# TIVA_SHIELD_Ver_2_0.net
KiCad netlist of a schematic drawn in EAGLE
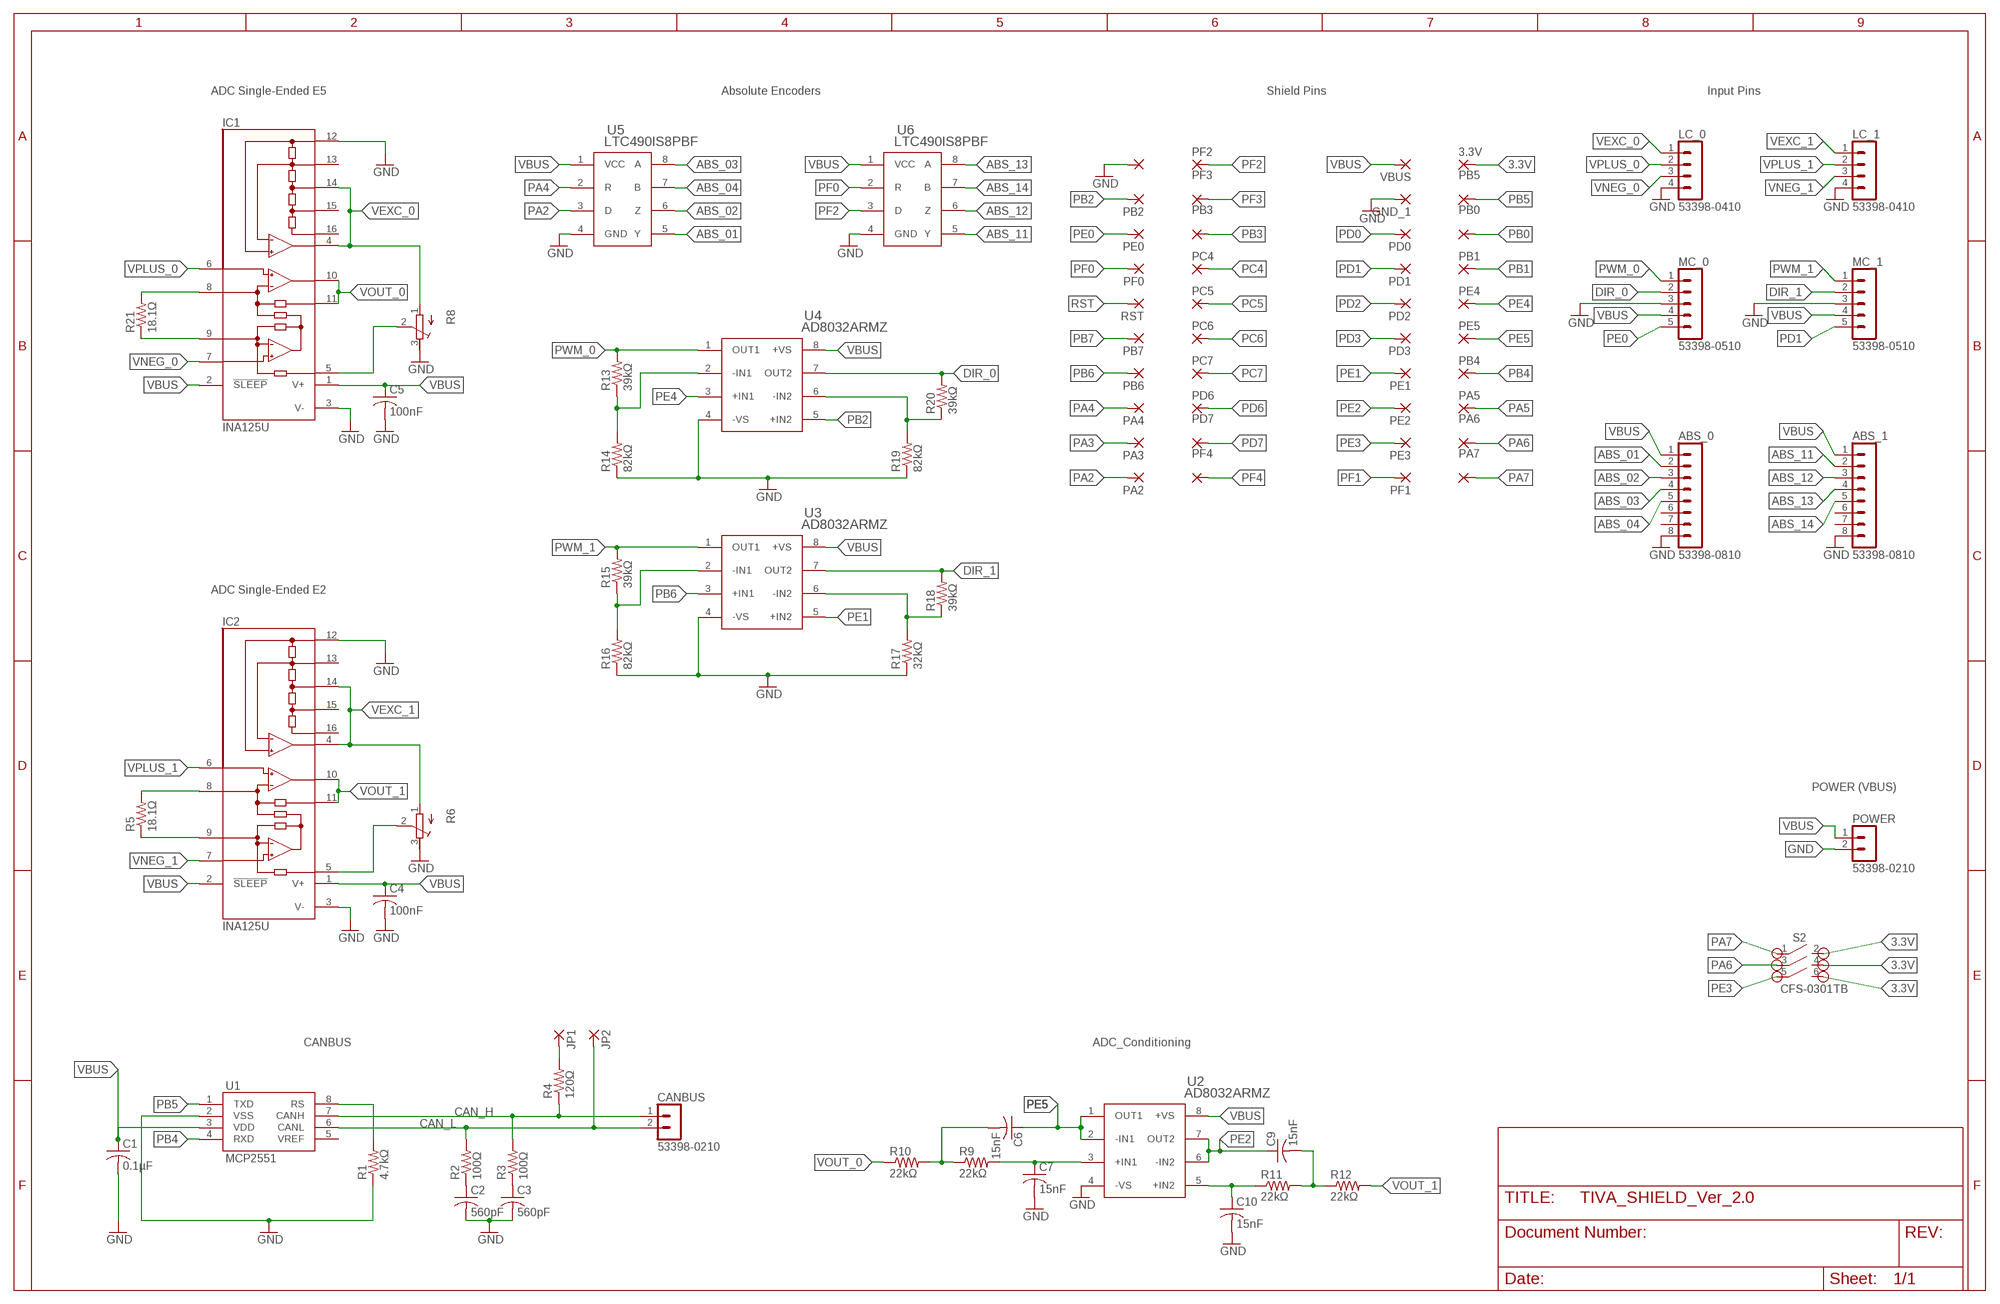
[diagram p0: schematic, sheet 1]

(export (version "E")
  (design (tool "Eeschema 10.0.6"))
  (components
    (comp (ref "3.3V")
      (value "1,6/0,9")
      (footprint "eagle-import:1,6_0,9")
      (libsource (lib "eagle-import") (part "1,6/0,9"))
    )
    (comp (ref "ABS_0")
      (value "53398-0810")
      (footprint "eagle-import:53398-0810")
      (libsource (lib "eagle-import") (part "53398-0810"))
    )
    (comp (ref "ABS_1")
      (value "53398-0810")
      (footprint "eagle-import:53398-0810")
      (libsource (lib "eagle-import") (part "53398-0810"))
    )
    (comp (ref "C1")
      (value "0.1µF")
      (footprint "eagle-import:C0805")
      (libsource (lib "eagle-import") (part "C-USC0805"))
    )
    (comp (ref "C2")
      (value "560pF")
      (footprint "eagle-import:C0805")
      (libsource (lib "eagle-import") (part "C-USC0805"))
    )
    (comp (ref "C3")
      (value "560pF")
      (footprint "eagle-import:C0805")
      (libsource (lib "eagle-import") (part "C-USC0805"))
    )
    (comp (ref "C4")
      (value "100nF")
      (footprint "eagle-import:C0805")
      (libsource (lib "eagle-import") (part "C-USC0805"))
    )
    (comp (ref "C5")
      (value "100nF")
      (footprint "eagle-import:C0805")
      (libsource (lib "eagle-import") (part "C-USC0805"))
    )
    (comp (ref "C6")
      (value "15nF")
      (footprint "eagle-import:C0805")
      (libsource (lib "eagle-import") (part "C-USC0805"))
    )
    (comp (ref "C7")
      (value "15nF")
      (footprint "eagle-import:C0805")
      (libsource (lib "eagle-import") (part "C-USC0805"))
    )
    (comp (ref "C9")
      (value "15nF")
      (footprint "eagle-import:C0805")
      (libsource (lib "eagle-import") (part "C-USC0805"))
    )
    (comp (ref "C10")
      (value "15nF")
      (footprint "eagle-import:C0805")
      (libsource (lib "eagle-import") (part "C-USC0805"))
    )
    (comp (ref "CANBUS")
      (value "53398-0210")
      (footprint "eagle-import:53398-0210")
      (libsource (lib "eagle-import") (part "53398-0210"))
    )
    (comp (ref "GND_0")
      (value "1,6/0,9")
      (footprint "eagle-import:1,6_0,9")
      (libsource (lib "eagle-import") (part "1,6/0,9"))
    )
    (comp (ref "GND_1")
      (value "1,6/0,9")
      (footprint "eagle-import:1,6_0,9")
      (libsource (lib "eagle-import") (part "1,6/0,9"))
    )
    (comp (ref "IC1")
      (value "INA125U")
      (footprint "eagle-import:SO16-1")
      (fields (field (name "MF") "TEXAS INSTRUMENT CONNECTORS"))
      (libsource (lib "eagle-import") (part "INA125U"))
    )
    (comp (ref "IC2")
      (value "INA125U")
      (footprint "eagle-import:SO16-1")
      (fields (field (name "MF") "TEXAS INSTRUMENT CONNECTORS"))
      (libsource (lib "eagle-import") (part "INA125U"))
    )
    (comp (ref "JP1")
      (value "1,6/0,9")
      (footprint "eagle-import:1,6_0,9")
      (libsource (lib "eagle-import") (part "1,6/0,9"))
    )
    (comp (ref "JP2")
      (value "1,6/0,9")
      (footprint "eagle-import:1,6_0,9")
      (libsource (lib "eagle-import") (part "1,6/0,9"))
    )
    (comp (ref "LC_0")
      (value "53398-0410")
      (footprint "eagle-import:53398-0410")
      (libsource (lib "eagle-import") (part "53398-0410"))
    )
    (comp (ref "LC_1")
      (value "53398-0410")
      (footprint "eagle-import:53398-0410")
      (libsource (lib "eagle-import") (part "53398-0410"))
    )
    (comp (ref "MC_0")
      (value "53398-0510")
      (footprint "eagle-import:53398-0510")
      (libsource (lib "eagle-import") (part "53398-0510"))
    )
    (comp (ref "MC_1")
      (value "53398-0510")
      (footprint "eagle-import:53398-0510")
      (libsource (lib "eagle-import") (part "53398-0510"))
    )
    (comp (ref "PA2")
      (value "1,6/0,9")
      (footprint "eagle-import:1,6_0,9")
      (libsource (lib "eagle-import") (part "1,6/0,9"))
    )
    (comp (ref "PA3")
      (value "1,6/0,9")
      (footprint "eagle-import:1,6_0,9")
      (libsource (lib "eagle-import") (part "1,6/0,9"))
    )
    (comp (ref "PA4")
      (value "1,6/0,9")
      (footprint "eagle-import:1,6_0,9")
      (libsource (lib "eagle-import") (part "1,6/0,9"))
    )
    (comp (ref "PA5")
      (value "1,6/0,9")
      (footprint "eagle-import:1,6_0,9")
      (libsource (lib "eagle-import") (part "1,6/0,9"))
    )
    (comp (ref "PA6")
      (value "1,6/0,9")
      (footprint "eagle-import:1,6_0,9")
      (libsource (lib "eagle-import") (part "1,6/0,9"))
    )
    (comp (ref "PA7")
      (value "1,6/0,9")
      (footprint "eagle-import:1,6_0,9")
      (libsource (lib "eagle-import") (part "1,6/0,9"))
    )
    (comp (ref "PB0")
      (value "1,6/0,9")
      (footprint "eagle-import:1,6_0,9")
      (libsource (lib "eagle-import") (part "1,6/0,9"))
    )
    (comp (ref "PB1")
      (value "1,6/0,9")
      (footprint "eagle-import:1,6_0,9")
      (libsource (lib "eagle-import") (part "1,6/0,9"))
    )
    (comp (ref "PB2")
      (value "1,6/0,9")
      (footprint "eagle-import:1,6_0,9")
      (libsource (lib "eagle-import") (part "1,6/0,9"))
    )
    (comp (ref "PB3")
      (value "1,6/0,9")
      (footprint "eagle-import:1,6_0,9")
      (libsource (lib "eagle-import") (part "1,6/0,9"))
    )
    (comp (ref "PB4")
      (value "1,6/0,9")
      (footprint "eagle-import:1,6_0,9")
      (libsource (lib "eagle-import") (part "1,6/0,9"))
    )
    (comp (ref "PB5")
      (value "1,6/0,9")
      (footprint "eagle-import:1,6_0,9")
      (libsource (lib "eagle-import") (part "1,6/0,9"))
    )
    (comp (ref "PB6")
      (value "1,6/0,9")
      (footprint "eagle-import:1,6_0,9")
      (libsource (lib "eagle-import") (part "1,6/0,9"))
    )
    (comp (ref "PB7")
      (value "1,6/0,9")
      (footprint "eagle-import:1,6_0,9")
      (libsource (lib "eagle-import") (part "1,6/0,9"))
    )
    (comp (ref "PC4")
      (value "1,6/0,9")
      (footprint "eagle-import:1,6_0,9")
      (libsource (lib "eagle-import") (part "1,6/0,9"))
    )
    (comp (ref "PC5")
      (value "1,6/0,9")
      (footprint "eagle-import:1,6_0,9")
      (libsource (lib "eagle-import") (part "1,6/0,9"))
    )
    (comp (ref "PC6")
      (value "1,6/0,9")
      (footprint "eagle-import:1,6_0,9")
      (libsource (lib "eagle-import") (part "1,6/0,9"))
    )
    (comp (ref "PC7")
      (value "1,6/0,9")
      (footprint "eagle-import:1,6_0,9")
      (libsource (lib "eagle-import") (part "1,6/0,9"))
    )
    (comp (ref "PD0")
      (value "1,6/0,9")
      (footprint "eagle-import:1,6_0,9")
      (libsource (lib "eagle-import") (part "1,6/0,9"))
    )
    (comp (ref "PD1")
      (value "1,6/0,9")
      (footprint "eagle-import:1,6_0,9")
      (libsource (lib "eagle-import") (part "1,6/0,9"))
    )
    (comp (ref "PD2")
      (value "1,6/0,9")
      (footprint "eagle-import:1,6_0,9")
      (libsource (lib "eagle-import") (part "1,6/0,9"))
    )
    (comp (ref "PD3")
      (value "1,6/0,9")
      (footprint "eagle-import:1,6_0,9")
      (libsource (lib "eagle-import") (part "1,6/0,9"))
    )
    (comp (ref "PD6")
      (value "1,6/0,9")
      (footprint "eagle-import:1,6_0,9")
      (libsource (lib "eagle-import") (part "1,6/0,9"))
    )
    (comp (ref "PD7")
      (value "1,6/0,9")
      (footprint "eagle-import:1,6_0,9")
      (libsource (lib "eagle-import") (part "1,6/0,9"))
    )
    (comp (ref "PE0")
      (value "1,6/0,9")
      (footprint "eagle-import:1,6_0,9")
      (libsource (lib "eagle-import") (part "1,6/0,9"))
    )
    (comp (ref "PE1")
      (value "1,6/0,9")
      (footprint "eagle-import:1,6_0,9")
      (libsource (lib "eagle-import") (part "1,6/0,9"))
    )
    (comp (ref "PE2")
      (value "1,6/0,9")
      (footprint "eagle-import:1,6_0,9")
      (libsource (lib "eagle-import") (part "1,6/0,9"))
    )
    (comp (ref "PE3")
      (value "1,6/0,9")
      (footprint "eagle-import:1,6_0,9")
      (libsource (lib "eagle-import") (part "1,6/0,9"))
    )
    (comp (ref "PE4")
      (value "1,6/0,9")
      (footprint "eagle-import:1,6_0,9")
      (libsource (lib "eagle-import") (part "1,6/0,9"))
    )
    (comp (ref "PE5")
      (value "1,6/0,9")
      (footprint "eagle-import:1,6_0,9")
      (libsource (lib "eagle-import") (part "1,6/0,9"))
    )
    (comp (ref "PF0")
      (value "1,6/0,9")
      (footprint "eagle-import:1,6_0,9")
      (libsource (lib "eagle-import") (part "1,6/0,9"))
    )
    (comp (ref "PF1")
      (value "1,6/0,9")
      (footprint "eagle-import:1,6_0,9")
      (libsource (lib "eagle-import") (part "1,6/0,9"))
    )
    (comp (ref "PF2")
      (value "1,6/0,9")
      (footprint "eagle-import:1,6_0,9")
      (libsource (lib "eagle-import") (part "1,6/0,9"))
    )
    (comp (ref "PF3")
      (value "1,6/0,9")
      (footprint "eagle-import:1,6_0,9")
      (libsource (lib "eagle-import") (part "1,6/0,9"))
    )
    (comp (ref "PF4")
      (value "1,6/0,9")
      (footprint "eagle-import:1,6_0,9")
      (libsource (lib "eagle-import") (part "1,6/0,9"))
    )
    (comp (ref "POWER")
      (value "53398-0210")
      (footprint "eagle-import:53398-0210")
      (libsource (lib "eagle-import") (part "53398-0210"))
    )
    (comp (ref "R1")
      (value "4.7kΩ")
      (footprint "eagle-import:R0805")
      (libsource (lib "eagle-import") (part "R-US_R0805"))
    )
    (comp (ref "R2")
      (value "100Ω")
      (footprint "eagle-import:R0805")
      (libsource (lib "eagle-import") (part "R-US_R0805"))
    )
    (comp (ref "R3")
      (value "100Ω")
      (footprint "eagle-import:R0805")
      (libsource (lib "eagle-import") (part "R-US_R0805"))
    )
    (comp (ref "R4")
      (value "120Ω")
      (footprint "eagle-import:R0805")
      (libsource (lib "eagle-import") (part "R-US_R0805"))
    )
    (comp (ref "R5")
      (value "18.1Ω")
      (footprint "eagle-import:R0805")
      (libsource (lib "eagle-import") (part "R-US_R0805"))
    )
    (comp (ref "R6")
      (value "R-TRIMM64W")
      (footprint "eagle-import:RTRIM64W")
      (libsource (lib "eagle-import") (part "R-TRIMM64W"))
    )
    (comp (ref "R8")
      (value "R-TRIMM64W")
      (footprint "eagle-import:RTRIM64W")
      (libsource (lib "eagle-import") (part "R-TRIMM64W"))
    )
    (comp (ref "R9")
      (value "22kΩ")
      (footprint "eagle-import:R0805")
      (libsource (lib "eagle-import") (part "R-US_R0805"))
    )
    (comp (ref "R10")
      (value "22kΩ")
      (footprint "eagle-import:R0805")
      (libsource (lib "eagle-import") (part "R-US_R0805"))
    )
    (comp (ref "R11")
      (value "22kΩ")
      (footprint "eagle-import:R0805")
      (libsource (lib "eagle-import") (part "R-US_R0805"))
    )
    (comp (ref "R12")
      (value "22kΩ")
      (footprint "eagle-import:R0805")
      (libsource (lib "eagle-import") (part "R-US_R0805"))
    )
    (comp (ref "R13")
      (value "39kΩ")
      (footprint "eagle-import:R0805")
      (libsource (lib "eagle-import") (part "R-US_R0805"))
    )
    (comp (ref "R14")
      (value "82kΩ")
      (footprint "eagle-import:R0805")
      (libsource (lib "eagle-import") (part "R-US_R0805"))
    )
    (comp (ref "R15")
      (value "39kΩ")
      (footprint "eagle-import:R0805")
      (libsource (lib "eagle-import") (part "R-US_R0805"))
    )
    (comp (ref "R16")
      (value "82kΩ")
      (footprint "eagle-import:R0805")
      (libsource (lib "eagle-import") (part "R-US_R0805"))
    )
    (comp (ref "R17")
      (value "32kΩ")
      (footprint "eagle-import:R0805")
      (libsource (lib "eagle-import") (part "R-US_R0805"))
    )
    (comp (ref "R18")
      (value "39kΩ")
      (footprint "eagle-import:R0805")
      (libsource (lib "eagle-import") (part "R-US_R0805"))
    )
    (comp (ref "R19")
      (value "82kΩ")
      (footprint "eagle-import:R0805")
      (libsource (lib "eagle-import") (part "R-US_R0805"))
    )
    (comp (ref "R20")
      (value "39kΩ")
      (footprint "eagle-import:R0805")
      (libsource (lib "eagle-import") (part "R-US_R0805"))
    )
    (comp (ref "R21")
      (value "18.1Ω")
      (footprint "eagle-import:R0805")
      (libsource (lib "eagle-import") (part "R-US_R0805"))
    )
    (comp (ref "RST")
      (value "1,6/0,9")
      (footprint "eagle-import:1,6_0,9")
      (libsource (lib "eagle-import") (part "1,6/0,9"))
    )
    (comp (ref "S2")
      (value "CFS-0301TB")
      (footprint "eagle-import:CFS-0301TB")
      (libsource (lib "eagle-import") (part "CFS-0301TBSMD"))
    )
    (comp (ref "U1")
      (value "MCP2551")
      (footprint "eagle-import:SO08")
      (libsource (lib "eagle-import") (part "MCP2551"))
    )
    (comp (ref "U2")
      (value "AD8032ARMZ")
      (footprint "eagle-import:RM_8")
      (libsource (lib "eagle-import") (part "AD8032ARMZ"))
    )
    (comp (ref "U3")
      (value "AD8032ARMZ")
      (footprint "eagle-import:RM_8")
      (libsource (lib "eagle-import") (part "AD8032ARMZ"))
    )
    (comp (ref "U4")
      (value "AD8032ARMZ")
      (footprint "eagle-import:RM_8")
      (libsource (lib "eagle-import") (part "AD8032ARMZ"))
    )
    (comp (ref "U5")
      (value "LTC490IS8PBF")
      (footprint "eagle-import:SO-8_S")
      (fields (field (name "MANUFACTURER_PART_NUMBER") "LTC490IS8#PBF"))
      (libsource (lib "eagle-import") (part "LTC490IS8PBF"))
    )
    (comp (ref "U6")
      (value "LTC490IS8PBF")
      (footprint "eagle-import:SO-8_S")
      (fields (field (name "MANUFACTURER_PART_NUMBER") "LTC490IS8#PBF"))
      (libsource (lib "eagle-import") (part "LTC490IS8PBF"))
    )
    (comp (ref "VBUS")
      (value "1,6/0,9")
      (footprint "eagle-import:1,6_0,9")
      (libsource (lib "eagle-import") (part "1,6/0,9"))
    )
  )
  (nets
    (net (code "1") (name "/CAN_H") (class "Default")
      (node (ref "CANBUS") (pin "1") (pinfunction "1_1") (pintype "passive"))
      (node (ref "R3") (pin "2") (pinfunction "2_2") (pintype "passive"))
      (node (ref "R4") (pin "1") (pinfunction "1_1") (pintype "passive"))
      (node (ref "U1") (pin "7") (pinfunction "CANH_7") (pintype "bidirectional"))
    )
    (net (code "2") (name "/CAN_L") (class "Default")
      (node (ref "CANBUS") (pin "2") (pinfunction "2_2") (pintype "passive"))
      (node (ref "JP2") (pin "1") (pinfunction "P_1") (pintype "passive"))
      (node (ref "R2") (pin "2") (pinfunction "2_2") (pintype "passive"))
      (node (ref "U1") (pin "6") (pinfunction "CANL_6") (pintype "bidirectional"))
    )
    (net (code "3") (name "3.3V") (class "Default")
      (node (ref "3.3V") (pin "1") (pinfunction "P_1") (pintype "passive"))
      (node (ref "S2") (pin "2") (pinfunction "2_2") (pintype "bidirectional"))
      (node (ref "S2") (pin "4") (pinfunction "4_4") (pintype "bidirectional"))
      (node (ref "S2") (pin "6") (pinfunction "6_6") (pintype "bidirectional"))
    )
    (net (code "4") (name "ABS_01") (class "Default")
      (node (ref "ABS_0") (pin "2") (pinfunction "2_2") (pintype "passive"))
      (node (ref "U5") (pin "5") (pinfunction "Y_5") (pintype "output"))
    )
    (net (code "5") (name "ABS_02") (class "Default")
      (node (ref "ABS_0") (pin "3") (pinfunction "3_3") (pintype "passive"))
      (node (ref "U5") (pin "6") (pinfunction "Z_6") (pintype "output"))
    )
    (net (code "6") (name "ABS_03") (class "Default")
      (node (ref "ABS_0") (pin "4") (pinfunction "4_4") (pintype "passive"))
      (node (ref "U5") (pin "8") (pinfunction "A_8") (pintype "input"))
    )
    (net (code "7") (name "ABS_04") (class "Default")
      (node (ref "ABS_0") (pin "5") (pinfunction "5_5") (pintype "passive"))
      (node (ref "U5") (pin "7") (pinfunction "B_7") (pintype "input"))
    )
    (net (code "8") (name "ABS_11") (class "Default")
      (node (ref "ABS_1") (pin "2") (pinfunction "2_2") (pintype "passive"))
      (node (ref "U6") (pin "5") (pinfunction "Y_5") (pintype "output"))
    )
    (net (code "9") (name "ABS_12") (class "Default")
      (node (ref "ABS_1") (pin "3") (pinfunction "3_3") (pintype "passive"))
      (node (ref "U6") (pin "6") (pinfunction "Z_6") (pintype "output"))
    )
    (net (code "10") (name "ABS_13") (class "Default")
      (node (ref "ABS_1") (pin "4") (pinfunction "4_4") (pintype "passive"))
      (node (ref "U6") (pin "8") (pinfunction "A_8") (pintype "input"))
    )
    (net (code "11") (name "ABS_14") (class "Default")
      (node (ref "ABS_1") (pin "5") (pinfunction "5_5") (pintype "passive"))
      (node (ref "U6") (pin "7") (pinfunction "B_7") (pintype "input"))
    )
    (net (code "12") (name "DIR_0") (class "Default")
      (node (ref "MC_0") (pin "2") (pinfunction "2_2") (pintype "passive"))
      (node (ref "R20") (pin "2") (pinfunction "2_2") (pintype "passive"))
      (node (ref "U4") (pin "7") (pinfunction "OUT2_7") (pintype "passive"))
    )
    (net (code "13") (name "DIR_1") (class "Default")
      (node (ref "MC_1") (pin "2") (pinfunction "2_2") (pintype "passive"))
      (node (ref "R18") (pin "2") (pinfunction "2_2") (pintype "passive"))
      (node (ref "U3") (pin "7") (pinfunction "OUT2_7") (pintype "passive"))
    )
    (net (code "14") (name "GND") (class "Default")
      (node (ref "ABS_0") (pin "8") (pinfunction "8_8") (pintype "passive"))
      (node (ref "ABS_1") (pin "8") (pinfunction "8_8") (pintype "passive"))
      (node (ref "C1") (pin "2") (pinfunction "2_2") (pintype "passive"))
      (node (ref "C10") (pin "2") (pinfunction "2_2") (pintype "passive"))
      (node (ref "C2") (pin "2") (pinfunction "2_2") (pintype "passive"))
      (node (ref "C3") (pin "2") (pinfunction "2_2") (pintype "passive"))
      (node (ref "C4") (pin "2") (pinfunction "2_2") (pintype "passive"))
      (node (ref "C5") (pin "2") (pinfunction "2_2") (pintype "passive"))
      (node (ref "C7") (pin "2") (pinfunction "2_2") (pintype "passive"))
      (node (ref "GND_0") (pin "1") (pinfunction "P_1") (pintype "passive"))
      (node (ref "GND_1") (pin "1") (pinfunction "P_1") (pintype "passive"))
      (node (ref "IC1") (pin "12") (pinfunction "REFCOM_12") (pintype "passive"))
      (node (ref "IC1") (pin "3") (pinfunction "V-_3") (pintype "power_in"))
      (node (ref "IC2") (pin "12") (pinfunction "REFCOM_12") (pintype "passive"))
      (node (ref "IC2") (pin "3") (pinfunction "V-_3") (pintype "power_in"))
      (node (ref "LC_0") (pin "4") (pinfunction "4_4") (pintype "passive"))
      (node (ref "LC_1") (pin "4") (pinfunction "4_4") (pintype "passive"))
      (node (ref "MC_0") (pin "3") (pinfunction "3_3") (pintype "passive"))
      (node (ref "MC_1") (pin "3") (pinfunction "3_3") (pintype "passive"))
      (node (ref "POWER") (pin "2") (pinfunction "2_2") (pintype "passive"))
      (node (ref "R1") (pin "1") (pinfunction "1_1") (pintype "passive"))
      (node (ref "R14") (pin "1") (pinfunction "1_1") (pintype "passive"))
      (node (ref "R16") (pin "1") (pinfunction "1_1") (pintype "passive"))
      (node (ref "R17") (pin "1") (pinfunction "1_1") (pintype "passive"))
      (node (ref "R19") (pin "1") (pinfunction "1_1") (pintype "passive"))
      (node (ref "R6") (pin "3") (pinfunction "E_3") (pintype "passive"))
      (node (ref "R8") (pin "3") (pinfunction "E_3") (pintype "passive"))
      (node (ref "U1") (pin "2") (pinfunction "VSS_2") (pintype "bidirectional"))
      (node (ref "U2") (pin "4") (pinfunction "-VS_4") (pintype "power_in"))
      (node (ref "U3") (pin "4") (pinfunction "-VS_4") (pintype "power_in"))
      (node (ref "U4") (pin "4") (pinfunction "-VS_4") (pintype "power_in"))
      (node (ref "U5") (pin "4") (pinfunction "GND_4") (pintype "power_in"))
      (node (ref "U6") (pin "4") (pinfunction "GND_4") (pintype "power_in"))
    )
    (net (code "15") (name "Net-(C2-Pad1)") (class "Default")
      (node (ref "C2") (pin "1") (pinfunction "1_1") (pintype "passive"))
      (node (ref "R2") (pin "1") (pinfunction "1_1") (pintype "passive"))
    )
    (net (code "16") (name "Net-(C3-Pad1)") (class "Default")
      (node (ref "C3") (pin "1") (pinfunction "1_1") (pintype "passive"))
      (node (ref "R3") (pin "1") (pinfunction "1_1") (pintype "passive"))
    )
    (net (code "17") (name "Net-(C6-Pad2)") (class "Default")
      (node (ref "C6") (pin "2") (pinfunction "2_2") (pintype "passive"))
      (node (ref "R10") (pin "2") (pinfunction "2_2") (pintype "passive"))
      (node (ref "R9") (pin "1") (pinfunction "1_1") (pintype "passive"))
    )
    (net (code "18") (name "Net-(C9-Pad2)") (class "Default")
      (node (ref "C9") (pin "2") (pinfunction "2_2") (pintype "passive"))
      (node (ref "R11") (pin "2") (pinfunction "2_2") (pintype "passive"))
      (node (ref "R12") (pin "1") (pinfunction "1_1") (pintype "passive"))
    )
    (net (code "19") (name "Net-(IC1-REF)") (class "Default")
      (node (ref "IC1") (pin "5") (pinfunction "REF_5") (pintype "passive"))
      (node (ref "R8") (pin "2") (pinfunction "S_2") (pintype "passive"))
    )
    (net (code "20") (name "Net-(IC1-RG-Pad8)") (class "Default")
      (node (ref "IC1") (pin "8") (pinfunction "RG_8") (pintype "passive"))
      (node (ref "R21") (pin "2") (pinfunction "2_2") (pintype "passive"))
    )
    (net (code "21") (name "Net-(IC1-RG-Pad9)") (class "Default")
      (node (ref "IC1") (pin "9") (pinfunction "RG_9") (pintype "passive"))
      (node (ref "R21") (pin "1") (pinfunction "1_1") (pintype "passive"))
    )
    (net (code "22") (name "Net-(IC2-REF)") (class "Default")
      (node (ref "IC2") (pin "5") (pinfunction "REF_5") (pintype "passive"))
      (node (ref "R6") (pin "2") (pinfunction "S_2") (pintype "passive"))
    )
    (net (code "23") (name "Net-(IC2-RG-Pad8)") (class "Default")
      (node (ref "IC2") (pin "8") (pinfunction "RG_8") (pintype "passive"))
      (node (ref "R5") (pin "2") (pinfunction "2_2") (pintype "passive"))
    )
    (net (code "24") (name "Net-(IC2-RG-Pad9)") (class "Default")
      (node (ref "IC2") (pin "9") (pinfunction "RG_9") (pintype "passive"))
      (node (ref "R5") (pin "1") (pinfunction "1_1") (pintype "passive"))
    )
    (net (code "25") (name "Net-(JP1-P)") (class "Default")
      (node (ref "JP1") (pin "1") (pinfunction "P_1") (pintype "passive"))
      (node (ref "R4") (pin "2") (pinfunction "2_2") (pintype "passive"))
    )
    (net (code "26") (name "Net-(U1-RS)") (class "Default")
      (node (ref "R1") (pin "2") (pinfunction "2_2") (pintype "passive"))
      (node (ref "U1") (pin "8") (pinfunction "RS_8") (pintype "bidirectional"))
    )
    (net (code "27") (name "Net-(U2-+IN1)") (class "Default")
      (node (ref "C7") (pin "1") (pinfunction "1_1") (pintype "passive"))
      (node (ref "R9") (pin "2") (pinfunction "2_2") (pintype "passive"))
      (node (ref "U2") (pin "3") (pinfunction "+IN1_3") (pintype "passive"))
    )
    (net (code "28") (name "Net-(U2-+IN2)") (class "Default")
      (node (ref "C10") (pin "1") (pinfunction "1_1") (pintype "passive"))
      (node (ref "R11") (pin "1") (pinfunction "1_1") (pintype "passive"))
      (node (ref "U2") (pin "5") (pinfunction "+IN2_5") (pintype "passive"))
    )
    (net (code "29") (name "Net-(U3--IN1)") (class "Default")
      (node (ref "R15") (pin "1") (pinfunction "1_1") (pintype "passive"))
      (node (ref "R16") (pin "2") (pinfunction "2_2") (pintype "passive"))
      (node (ref "U3") (pin "2") (pinfunction "-IN1_2") (pintype "passive"))
    )
    (net (code "30") (name "Net-(U3--IN2)") (class "Default")
      (node (ref "R17") (pin "2") (pinfunction "2_2") (pintype "passive"))
      (node (ref "R18") (pin "1") (pinfunction "1_1") (pintype "passive"))
      (node (ref "U3") (pin "6") (pinfunction "-IN2_6") (pintype "passive"))
    )
    (net (code "31") (name "Net-(U4--IN1)") (class "Default")
      (node (ref "R13") (pin "1") (pinfunction "1_1") (pintype "passive"))
      (node (ref "R14") (pin "2") (pinfunction "2_2") (pintype "passive"))
      (node (ref "U4") (pin "2") (pinfunction "-IN1_2") (pintype "passive"))
    )
    (net (code "32") (name "Net-(U4--IN2)") (class "Default")
      (node (ref "R19") (pin "2") (pinfunction "2_2") (pintype "passive"))
      (node (ref "R20") (pin "1") (pinfunction "1_1") (pintype "passive"))
      (node (ref "U4") (pin "6") (pinfunction "-IN2_6") (pintype "passive"))
    )
    (net (code "33") (name "PA2") (class "Default")
      (node (ref "PA2") (pin "1") (pinfunction "P_1") (pintype "passive"))
      (node (ref "U5") (pin "3") (pinfunction "D_3") (pintype "input"))
    )
    (net (code "34") (name "PA3") (class "Default")
      (node (ref "PA3") (pin "1") (pinfunction "P_1") (pintype "passive"))
    )
    (net (code "35") (name "PA4") (class "Default")
      (node (ref "PA4") (pin "1") (pinfunction "P_1") (pintype "passive"))
      (node (ref "U5") (pin "2") (pinfunction "R_2") (pintype "output"))
    )
    (net (code "36") (name "PA5") (class "Default")
      (node (ref "PA5") (pin "1") (pinfunction "P_1") (pintype "passive"))
    )
    (net (code "37") (name "PA6") (class "Default")
      (node (ref "PA6") (pin "1") (pinfunction "P_1") (pintype "passive"))
      (node (ref "S2") (pin "3") (pinfunction "3_3") (pintype "bidirectional"))
    )
    (net (code "38") (name "PA7") (class "Default")
      (node (ref "PA7") (pin "1") (pinfunction "P_1") (pintype "passive"))
      (node (ref "S2") (pin "1") (pinfunction "1_1") (pintype "bidirectional"))
    )
    (net (code "39") (name "PB0") (class "Default")
      (node (ref "PB0") (pin "1") (pinfunction "P_1") (pintype "passive"))
    )
    (net (code "40") (name "PB1") (class "Default")
      (node (ref "PB1") (pin "1") (pinfunction "P_1") (pintype "passive"))
    )
    (net (code "41") (name "PB2") (class "Default")
      (node (ref "PB2") (pin "1") (pinfunction "P_1") (pintype "passive"))
      (node (ref "U4") (pin "5") (pinfunction "+IN2_5") (pintype "passive"))
    )
    (net (code "42") (name "PB3") (class "Default")
      (node (ref "PB3") (pin "1") (pinfunction "P_1") (pintype "passive"))
    )
    (net (code "43") (name "PB4") (class "Default")
      (node (ref "PB4") (pin "1") (pinfunction "P_1") (pintype "passive"))
      (node (ref "U1") (pin "4") (pinfunction "RXD_4") (pintype "bidirectional"))
    )
    (net (code "44") (name "PB5") (class "Default")
      (node (ref "PB5") (pin "1") (pinfunction "P_1") (pintype "passive"))
      (node (ref "U1") (pin "1") (pinfunction "TXD_1") (pintype "bidirectional"))
    )
    (net (code "45") (name "PB6") (class "Default")
      (node (ref "PB6") (pin "1") (pinfunction "P_1") (pintype "passive"))
      (node (ref "U3") (pin "3") (pinfunction "+IN1_3") (pintype "passive"))
    )
    (net (code "46") (name "PB7") (class "Default")
      (node (ref "PB7") (pin "1") (pinfunction "P_1") (pintype "passive"))
    )
    (net (code "47") (name "PC4") (class "Default")
      (node (ref "PC4") (pin "1") (pinfunction "P_1") (pintype "passive"))
    )
    (net (code "48") (name "PC5") (class "Default")
      (node (ref "PC5") (pin "1") (pinfunction "P_1") (pintype "passive"))
    )
    (net (code "49") (name "PC6") (class "Default")
      (node (ref "PC6") (pin "1") (pinfunction "P_1") (pintype "passive"))
    )
    (net (code "50") (name "PC7") (class "Default")
      (node (ref "PC7") (pin "1") (pinfunction "P_1") (pintype "passive"))
    )
    (net (code "51") (name "PD0") (class "Default")
      (node (ref "PD0") (pin "1") (pinfunction "P_1") (pintype "passive"))
    )
    (net (code "52") (name "PD1") (class "Default")
      (node (ref "MC_1") (pin "5") (pinfunction "5_5") (pintype "passive"))
      (node (ref "PD1") (pin "1") (pinfunction "P_1") (pintype "passive"))
    )
    (net (code "53") (name "PD2") (class "Default")
      (node (ref "PD2") (pin "1") (pinfunction "P_1") (pintype "passive"))
    )
    (net (code "54") (name "PD3") (class "Default")
      (node (ref "PD3") (pin "1") (pinfunction "P_1") (pintype "passive"))
    )
    (net (code "55") (name "PD6") (class "Default")
      (node (ref "PD6") (pin "1") (pinfunction "P_1") (pintype "passive"))
    )
    (net (code "56") (name "PD7") (class "Default")
      (node (ref "PD7") (pin "1") (pinfunction "P_1") (pintype "passive"))
    )
    (net (code "57") (name "PE0") (class "Default")
      (node (ref "MC_0") (pin "5") (pinfunction "5_5") (pintype "passive"))
      (node (ref "PE0") (pin "1") (pinfunction "P_1") (pintype "passive"))
    )
    (net (code "58") (name "PE1") (class "Default")
      (node (ref "PE1") (pin "1") (pinfunction "P_1") (pintype "passive"))
      (node (ref "U3") (pin "5") (pinfunction "+IN2_5") (pintype "passive"))
    )
    (net (code "59") (name "PE2") (class "Default")
      (node (ref "C9") (pin "1") (pinfunction "1_1") (pintype "passive"))
      (node (ref "PE2") (pin "1") (pinfunction "P_1") (pintype "passive"))
      (node (ref "U2") (pin "6") (pinfunction "-IN2_6") (pintype "passive"))
      (node (ref "U2") (pin "7") (pinfunction "OUT2_7") (pintype "passive"))
    )
    (net (code "60") (name "PE3") (class "Default")
      (node (ref "PE3") (pin "1") (pinfunction "P_1") (pintype "passive"))
      (node (ref "S2") (pin "5") (pinfunction "5_5") (pintype "bidirectional"))
    )
    (net (code "61") (name "PE4") (class "Default")
      (node (ref "PE4") (pin "1") (pinfunction "P_1") (pintype "passive"))
      (node (ref "U4") (pin "3") (pinfunction "+IN1_3") (pintype "passive"))
    )
    (net (code "62") (name "PE5") (class "Default")
      (node (ref "C6") (pin "1") (pinfunction "1_1") (pintype "passive"))
      (node (ref "PE5") (pin "1") (pinfunction "P_1") (pintype "passive"))
      (node (ref "U2") (pin "1") (pinfunction "OUT1_1") (pintype "passive"))
      (node (ref "U2") (pin "2") (pinfunction "-IN1_2") (pintype "passive"))
    )
    (net (code "63") (name "PF0") (class "Default")
      (node (ref "PF0") (pin "1") (pinfunction "P_1") (pintype "passive"))
      (node (ref "U6") (pin "2") (pinfunction "R_2") (pintype "output"))
    )
    (net (code "64") (name "PF1") (class "Default")
      (node (ref "PF1") (pin "1") (pinfunction "P_1") (pintype "passive"))
    )
    (net (code "65") (name "PF2") (class "Default")
      (node (ref "PF2") (pin "1") (pinfunction "P_1") (pintype "passive"))
      (node (ref "U6") (pin "3") (pinfunction "D_3") (pintype "input"))
    )
    (net (code "66") (name "PF3") (class "Default")
      (node (ref "PF3") (pin "1") (pinfunction "P_1") (pintype "passive"))
    )
    (net (code "67") (name "PF4") (class "Default")
      (node (ref "PF4") (pin "1") (pinfunction "P_1") (pintype "passive"))
    )
    (net (code "68") (name "PWM_0") (class "Default")
      (node (ref "MC_0") (pin "1") (pinfunction "1_1") (pintype "passive"))
      (node (ref "R13") (pin "2") (pinfunction "2_2") (pintype "passive"))
      (node (ref "U4") (pin "1") (pinfunction "OUT1_1") (pintype "passive"))
    )
    (net (code "69") (name "PWM_1") (class "Default")
      (node (ref "MC_1") (pin "1") (pinfunction "1_1") (pintype "passive"))
      (node (ref "R15") (pin "2") (pinfunction "2_2") (pintype "passive"))
      (node (ref "U3") (pin "1") (pinfunction "OUT1_1") (pintype "passive"))
    )
    (net (code "70") (name "RST") (class "Default")
      (node (ref "RST") (pin "1") (pinfunction "P_1") (pintype "passive"))
    )
    (net (code "71") (name "VBUS") (class "Default")
      (node (ref "ABS_0") (pin "1") (pinfunction "1_1") (pintype "passive"))
      (node (ref "ABS_1") (pin "1") (pinfunction "1_1") (pintype "passive"))
      (node (ref "C1") (pin "1") (pinfunction "1_1") (pintype "passive"))
      (node (ref "C4") (pin "1") (pinfunction "1_1") (pintype "passive"))
      (node (ref "C5") (pin "1") (pinfunction "1_1") (pintype "passive"))
      (node (ref "IC1") (pin "1") (pinfunction "V+_1") (pintype "power_in"))
      (node (ref "IC1") (pin "2") (pinfunction "~{SLEEP}_2") (pintype "input"))
      (node (ref "IC2") (pin "1") (pinfunction "V+_1") (pintype "power_in"))
      (node (ref "IC2") (pin "2") (pinfunction "~{SLEEP}_2") (pintype "input"))
      (node (ref "MC_0") (pin "4") (pinfunction "4_4") (pintype "passive"))
      (node (ref "MC_1") (pin "4") (pinfunction "4_4") (pintype "passive"))
      (node (ref "POWER") (pin "1") (pinfunction "1_1") (pintype "passive"))
      (node (ref "U1") (pin "3") (pinfunction "VDD_3") (pintype "bidirectional"))
      (node (ref "U2") (pin "8") (pinfunction "+VS_8") (pintype "power_in"))
      (node (ref "U3") (pin "8") (pinfunction "+VS_8") (pintype "power_in"))
      (node (ref "U4") (pin "8") (pinfunction "+VS_8") (pintype "power_in"))
      (node (ref "U5") (pin "1") (pinfunction "VCC_1") (pintype "power_in"))
      (node (ref "U6") (pin "1") (pinfunction "VCC_1") (pintype "power_in"))
      (node (ref "VBUS") (pin "1") (pinfunction "P_1") (pintype "passive"))
    )
    (net (code "72") (name "VEXC_0") (class "Default")
      (node (ref "IC1") (pin "14") (pinfunction "REF2.5_14") (pintype "output"))
      (node (ref "IC1") (pin "4") (pinfunction "REFOUT_4") (pintype "output"))
      (node (ref "LC_0") (pin "1") (pinfunction "1_1") (pintype "passive"))
      (node (ref "R8") (pin "1") (pinfunction "A_1") (pintype "passive"))
    )
    (net (code "73") (name "VEXC_1") (class "Default")
      (node (ref "IC2") (pin "14") (pinfunction "REF2.5_14") (pintype "output"))
      (node (ref "IC2") (pin "4") (pinfunction "REFOUT_4") (pintype "output"))
      (node (ref "LC_1") (pin "1") (pinfunction "1_1") (pintype "passive"))
      (node (ref "R6") (pin "1") (pinfunction "A_1") (pintype "passive"))
    )
    (net (code "74") (name "VNEG_0") (class "Default")
      (node (ref "IC1") (pin "7") (pinfunction "-IN_7") (pintype "input"))
      (node (ref "LC_0") (pin "3") (pinfunction "3_3") (pintype "passive"))
    )
    (net (code "75") (name "VNEG_1") (class "Default")
      (node (ref "IC2") (pin "7") (pinfunction "-IN_7") (pintype "input"))
      (node (ref "LC_1") (pin "3") (pinfunction "3_3") (pintype "passive"))
    )
    (net (code "76") (name "VOUT_0") (class "Default")
      (node (ref "IC1") (pin "10") (pinfunction "OUT_10") (pintype "output"))
      (node (ref "IC1") (pin "11") (pinfunction "SENSE_11") (pintype "passive"))
      (node (ref "R10") (pin "1") (pinfunction "1_1") (pintype "passive"))
    )
    (net (code "77") (name "VOUT_1") (class "Default")
      (node (ref "IC2") (pin "10") (pinfunction "OUT_10") (pintype "output"))
      (node (ref "IC2") (pin "11") (pinfunction "SENSE_11") (pintype "passive"))
      (node (ref "R12") (pin "2") (pinfunction "2_2") (pintype "passive"))
    )
    (net (code "78") (name "VPLUS_0") (class "Default")
      (node (ref "IC1") (pin "6") (pinfunction "+IN_6") (pintype "input"))
      (node (ref "LC_0") (pin "2") (pinfunction "2_2") (pintype "passive"))
    )
    (net (code "79") (name "VPLUS_1") (class "Default")
      (node (ref "IC2") (pin "6") (pinfunction "+IN_6") (pintype "input"))
      (node (ref "LC_1") (pin "2") (pinfunction "2_2") (pintype "passive"))
    )
    (net (code "80") (name "unconnected-(ABS_0-Pad6)") (class "Default")
      (node (ref "ABS_0") (pin "6") (pinfunction "6_6") (pintype "passive"))
    )
    (net (code "81") (name "unconnected-(ABS_0-Pad7)") (class "Default")
      (node (ref "ABS_0") (pin "7") (pinfunction "7_7") (pintype "passive"))
    )
    (net (code "82") (name "unconnected-(ABS_1-Pad6)") (class "Default")
      (node (ref "ABS_1") (pin "6") (pinfunction "6_6") (pintype "passive"))
    )
    (net (code "83") (name "unconnected-(ABS_1-Pad7)") (class "Default")
      (node (ref "ABS_1") (pin "7") (pinfunction "7_7") (pintype "passive"))
    )
    (net (code "84") (name "unconnected-(IC1-REF5-Pad15)") (class "Default")
      (node (ref "IC1") (pin "15") (pinfunction "REF5_15") (pintype "output"))
    )
    (net (code "85") (name "unconnected-(IC1-REF10-Pad16)") (class "Default")
      (node (ref "IC1") (pin "16") (pinfunction "REF10_16") (pintype "output"))
    )
    (net (code "86") (name "unconnected-(IC1-REFBG-Pad13)") (class "Default")
      (node (ref "IC1") (pin "13") (pinfunction "REFBG_13") (pintype "output"))
    )
    (net (code "87") (name "unconnected-(IC2-REF5-Pad15)") (class "Default")
      (node (ref "IC2") (pin "15") (pinfunction "REF5_15") (pintype "output"))
    )
    (net (code "88") (name "unconnected-(IC2-REF10-Pad16)") (class "Default")
      (node (ref "IC2") (pin "16") (pinfunction "REF10_16") (pintype "output"))
    )
    (net (code "89") (name "unconnected-(IC2-REFBG-Pad13)") (class "Default")
      (node (ref "IC2") (pin "13") (pinfunction "REFBG_13") (pintype "output"))
    )
    (net (code "90") (name "unconnected-(U1-VREF-Pad5)") (class "Default")
      (node (ref "U1") (pin "5") (pinfunction "VREF_5") (pintype "bidirectional"))
    )
  )
)
